# adc_24_bit_arduino-shield_v5.net
KiCad netlist of a schematic drawn in EAGLE
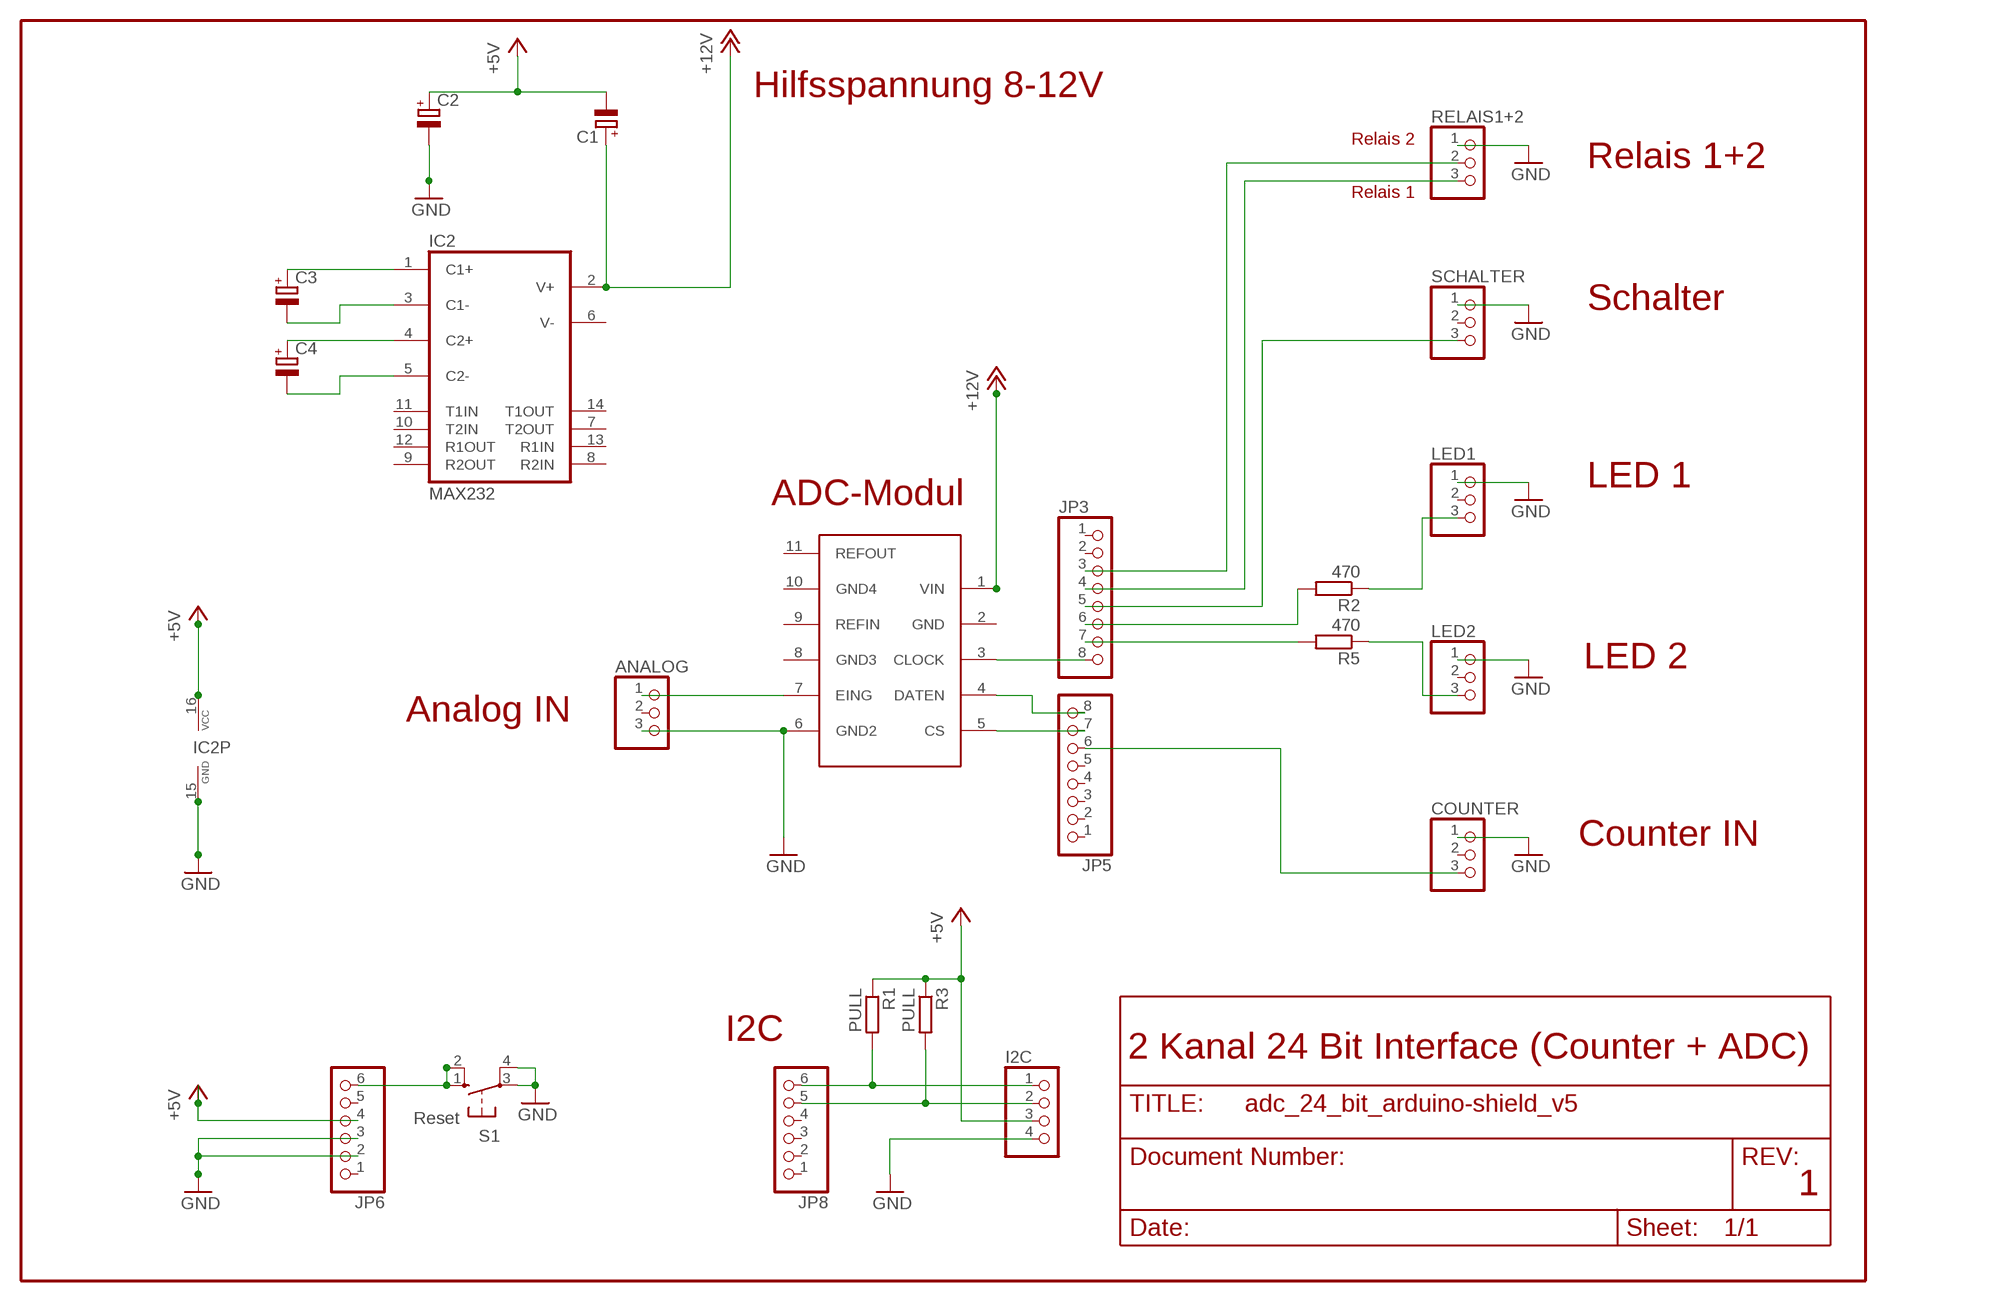
[diagram p0: schematic, sheet 1]

(export (version "E")
  (design (tool "Eeschema 10.0.6"))
  (components
    (comp (ref "ANALOG")
      (value "PINHD-1X3")
      (footprint "eagle-import:1X03")
      (libsource (lib "eagle-import") (part "PINHD-1X3"))
    )
    (comp (ref "C1")
      (value "CPOL-EUE2-4")
      (footprint "eagle-import:E2-4")
      (libsource (lib "eagle-import") (part "CPOL-EUE2-4"))
    )
    (comp (ref "C2")
      (value "CPOL-EUE2-4")
      (footprint "eagle-import:E2-4")
      (libsource (lib "eagle-import") (part "CPOL-EUE2-4"))
    )
    (comp (ref "C3")
      (value "CPOL-EUE2-4")
      (footprint "eagle-import:E2-4")
      (libsource (lib "eagle-import") (part "CPOL-EUE2-4"))
    )
    (comp (ref "C4")
      (value "CPOL-EUE2-4")
      (footprint "eagle-import:E2-4")
      (libsource (lib "eagle-import") (part "CPOL-EUE2-4"))
    )
    (comp (ref "COUNTER")
      (value "PINHD-1X3")
      (footprint "eagle-import:1X03")
      (libsource (lib "eagle-import") (part "PINHD-1X3"))
    )
    (comp (ref "I2C")
      (value "PINHD-1X4")
      (footprint "eagle-import:1X04")
      (libsource (lib "eagle-import") (part "PINHD-1X4"))
    )
    (comp (ref "IC1")
      (value "MODUL")
      (footprint "eagle-import:TEST")
      (libsource (lib "eagle-import") (part "MODUL"))
    )
    (comp (ref "IC2")
      (value "MAX232")
      (footprint "eagle-import:DIL16")
      (libsource (lib "eagle-import") (part "MAX232"))
    )
    (comp (ref "JP3")
      (value "PINHD-1X8CLEANBIG")
      (footprint "eagle-import:1X08-CLEANBIG")
      (libsource (lib "eagle-import") (part "PINHD-1X8CLEANBIG"))
    )
    (comp (ref "JP5")
      (value "PINHD-1X8CLEANBIG")
      (footprint "eagle-import:1X08-CLEANBIG")
      (libsource (lib "eagle-import") (part "PINHD-1X8CLEANBIG"))
    )
    (comp (ref "JP6")
      (value "PINHD-1X6CB")
      (footprint "eagle-import:1X06-CLEANBIG")
      (libsource (lib "eagle-import") (part "PINHD-1X6CB"))
    )
    (comp (ref "JP8")
      (value "PINHD-1X6CB")
      (footprint "eagle-import:1X06-CLEANBIG")
      (libsource (lib "eagle-import") (part "PINHD-1X6CB"))
    )
    (comp (ref "LED1")
      (value "PINHD-1X3")
      (footprint "eagle-import:1X03")
      (libsource (lib "eagle-import") (part "PINHD-1X3"))
    )
    (comp (ref "LED2")
      (value "PINHD-1X3")
      (footprint "eagle-import:1X03")
      (libsource (lib "eagle-import") (part "PINHD-1X3"))
    )
    (comp (ref "R1")
      (value "PULL")
      (footprint "eagle-import:0207_15")
      (libsource (lib "eagle-import") (part "R-EU_0207/15"))
    )
    (comp (ref "R2")
      (value "470")
      (footprint "eagle-import:0207_15")
      (libsource (lib "eagle-import") (part "R-EU_0207/15"))
    )
    (comp (ref "R3")
      (value "PULL")
      (footprint "eagle-import:0207_15")
      (libsource (lib "eagle-import") (part "R-EU_0207/15"))
    )
    (comp (ref "R5")
      (value "470")
      (footprint "eagle-import:0207_15")
      (libsource (lib "eagle-import") (part "R-EU_0207/15"))
    )
    (comp (ref "RELAIS1+2")
      (value "PINHD-1X3")
      (footprint "eagle-import:1X03")
      (libsource (lib "eagle-import") (part "PINHD-1X3"))
    )
    (comp (ref "S1")
      (value "Reset")
      (footprint "eagle-import:B3F-10XX")
      (libsource (lib "eagle-import") (part "10-XX"))
    )
    (comp (ref "SCHALTER")
      (value "PINHD-1X3")
      (footprint "eagle-import:1X03")
      (libsource (lib "eagle-import") (part "PINHD-1X3"))
    )
  )
  (nets
    (net (code "1") (name "+5V") (class "Default")
      (node (ref "C1") (pin "-") (pinfunction "-_-") (pintype "passive"))
      (node (ref "C2") (pin "+") (pinfunction "+_+") (pintype "passive"))
      (node (ref "I2C") (pin "3") (pinfunction "3_3") (pintype "passive"))
      (node (ref "IC2") (pin "16") (pinfunction "VCC_16") (pintype "power_in"))
      (node (ref "JP6") (pin "4") (pinfunction "4_4") (pintype "passive"))
      (node (ref "R1") (pin "1") (pinfunction "1_1") (pintype "passive"))
      (node (ref "R3") (pin "1") (pinfunction "1_1") (pintype "passive"))
    )
    (net (code "2") (name "+12V") (class "Default")
      (node (ref "C1") (pin "+") (pinfunction "+_+") (pintype "passive"))
      (node (ref "IC1") (pin "1") (pinfunction "VIN_1") (pintype "bidirectional"))
      (node (ref "IC2") (pin "2") (pinfunction "V+_2") (pintype "bidirectional"))
    )
    (net (code "3") (name "GND") (class "Default")
      (node (ref "ANALOG") (pin "3") (pinfunction "3_3") (pintype "passive"))
      (node (ref "C2") (pin "-") (pinfunction "-_-") (pintype "passive"))
      (node (ref "COUNTER") (pin "1") (pinfunction "1_1") (pintype "passive"))
      (node (ref "I2C") (pin "4") (pinfunction "4_4") (pintype "passive"))
      (node (ref "IC1") (pin "6") (pinfunction "GND2_6") (pintype "bidirectional"))
      (node (ref "IC2") (pin "15") (pinfunction "GND_15") (pintype "power_in"))
      (node (ref "JP6") (pin "2") (pinfunction "2_2") (pintype "passive"))
      (node (ref "JP6") (pin "3") (pinfunction "3_3") (pintype "passive"))
      (node (ref "LED1") (pin "1") (pinfunction "1_1") (pintype "passive"))
      (node (ref "LED2") (pin "1") (pinfunction "1_1") (pintype "passive"))
      (node (ref "RELAIS1+2") (pin "1") (pinfunction "1_1") (pintype "passive"))
      (node (ref "S1") (pin "3") (pinfunction "P_3") (pintype "passive"))
      (node (ref "S1") (pin "4") (pinfunction "P1_4") (pintype "passive"))
      (node (ref "SCHALTER") (pin "1") (pinfunction "1_1") (pintype "passive"))
    )
    (net (code "4") (name "Net-(COUNTER-Pad3)") (class "Default")
      (node (ref "COUNTER") (pin "3") (pinfunction "3_3") (pintype "passive"))
      (node (ref "JP5") (pin "6") (pinfunction "6_6") (pintype "passive"))
    )
    (net (code "5") (name "Net-(I2C-Pad1)") (class "Default")
      (node (ref "I2C") (pin "1") (pinfunction "1_1") (pintype "passive"))
      (node (ref "JP8") (pin "6") (pinfunction "6_6") (pintype "passive"))
      (node (ref "R1") (pin "2") (pinfunction "2_2") (pintype "passive"))
    )
    (net (code "6") (name "Net-(I2C-Pad2)") (class "Default")
      (node (ref "I2C") (pin "2") (pinfunction "2_2") (pintype "passive"))
      (node (ref "JP8") (pin "5") (pinfunction "5_5") (pintype "passive"))
      (node (ref "R3") (pin "2") (pinfunction "2_2") (pintype "passive"))
    )
    (net (code "7") (name "Net-(IC1-CLOCK)") (class "Default")
      (node (ref "IC1") (pin "3") (pinfunction "CLOCK_3") (pintype "bidirectional"))
      (node (ref "JP3") (pin "8") (pinfunction "8_8") (pintype "passive"))
    )
    (net (code "8") (name "Net-(IC1-CS)") (class "Default")
      (node (ref "IC1") (pin "5") (pinfunction "CS_5") (pintype "bidirectional"))
      (node (ref "JP5") (pin "7") (pinfunction "7_7") (pintype "passive"))
    )
    (net (code "9") (name "Net-(IC1-DATEN)") (class "Default")
      (node (ref "IC1") (pin "4") (pinfunction "DATEN_4") (pintype "bidirectional"))
      (node (ref "JP5") (pin "8") (pinfunction "8_8") (pintype "passive"))
    )
    (net (code "10") (name "Net-(IC1-EING)") (class "Default")
      (node (ref "ANALOG") (pin "1") (pinfunction "1_1") (pintype "passive"))
      (node (ref "IC1") (pin "7") (pinfunction "EING_7") (pintype "bidirectional"))
    )
    (net (code "11") (name "Net-(IC2A-C1+)") (class "Default")
      (node (ref "C3") (pin "+") (pinfunction "+_+") (pintype "passive"))
      (node (ref "IC2") (pin "1") (pinfunction "C1+_1") (pintype "bidirectional"))
    )
    (net (code "12") (name "Net-(IC2A-C1-)") (class "Default")
      (node (ref "C3") (pin "-") (pinfunction "-_-") (pintype "passive"))
      (node (ref "IC2") (pin "3") (pinfunction "C1-_3") (pintype "bidirectional"))
    )
    (net (code "13") (name "Net-(IC2A-C2+)") (class "Default")
      (node (ref "C4") (pin "+") (pinfunction "+_+") (pintype "passive"))
      (node (ref "IC2") (pin "4") (pinfunction "C2+_4") (pintype "bidirectional"))
    )
    (net (code "14") (name "Net-(IC2A-C2-)") (class "Default")
      (node (ref "C4") (pin "-") (pinfunction "-_-") (pintype "passive"))
      (node (ref "IC2") (pin "5") (pinfunction "C2-_5") (pintype "bidirectional"))
    )
    (net (code "15") (name "Net-(JP3-Pad3)") (class "Default")
      (node (ref "JP3") (pin "3") (pinfunction "3_3") (pintype "passive"))
      (node (ref "RELAIS1+2") (pin "2") (pinfunction "2_2") (pintype "passive"))
    )
    (net (code "16") (name "Net-(JP3-Pad4)") (class "Default")
      (node (ref "JP3") (pin "4") (pinfunction "4_4") (pintype "passive"))
      (node (ref "RELAIS1+2") (pin "3") (pinfunction "3_3") (pintype "passive"))
    )
    (net (code "17") (name "Net-(JP3-Pad5)") (class "Default")
      (node (ref "JP3") (pin "5") (pinfunction "5_5") (pintype "passive"))
      (node (ref "SCHALTER") (pin "3") (pinfunction "3_3") (pintype "passive"))
    )
    (net (code "18") (name "Net-(JP3-Pad6)") (class "Default")
      (node (ref "JP3") (pin "6") (pinfunction "6_6") (pintype "passive"))
      (node (ref "R2") (pin "2") (pinfunction "2_2") (pintype "passive"))
    )
    (net (code "19") (name "Net-(JP3-Pad7)") (class "Default")
      (node (ref "JP3") (pin "7") (pinfunction "7_7") (pintype "passive"))
      (node (ref "R5") (pin "2") (pinfunction "2_2") (pintype "passive"))
    )
    (net (code "20") (name "Net-(LED1-Pad3)") (class "Default")
      (node (ref "LED1") (pin "3") (pinfunction "3_3") (pintype "passive"))
      (node (ref "R2") (pin "1") (pinfunction "1_1") (pintype "passive"))
    )
    (net (code "21") (name "Net-(LED2-Pad3)") (class "Default")
      (node (ref "LED2") (pin "3") (pinfunction "3_3") (pintype "passive"))
      (node (ref "R5") (pin "1") (pinfunction "1_1") (pintype "passive"))
    )
    (net (code "22") (name "Net-(S1-S)") (class "Default")
      (node (ref "JP6") (pin "6") (pinfunction "6_6") (pintype "passive"))
      (node (ref "S1") (pin "1") (pinfunction "S_1") (pintype "passive"))
      (node (ref "S1") (pin "2") (pinfunction "S1_2") (pintype "passive"))
    )
    (net (code "23") (name "unconnected-(ANALOG-Pad2)") (class "Default")
      (node (ref "ANALOG") (pin "2") (pinfunction "2_2") (pintype "passive"))
    )
    (net (code "24") (name "unconnected-(COUNTER-Pad2)") (class "Default")
      (node (ref "COUNTER") (pin "2") (pinfunction "2_2") (pintype "passive"))
    )
    (net (code "25") (name "unconnected-(IC1-GND-Pad2)") (class "Default")
      (node (ref "IC1") (pin "2") (pinfunction "GND_2") (pintype "bidirectional"))
    )
    (net (code "26") (name "unconnected-(IC1-GND3-Pad8)") (class "Default")
      (node (ref "IC1") (pin "8") (pinfunction "GND3_8") (pintype "bidirectional"))
    )
    (net (code "27") (name "unconnected-(IC1-GND4-Pad10)") (class "Default")
      (node (ref "IC1") (pin "10") (pinfunction "GND4_10") (pintype "bidirectional"))
    )
    (net (code "28") (name "unconnected-(IC1-REFIN-Pad9)") (class "Default")
      (node (ref "IC1") (pin "9") (pinfunction "REFIN_9") (pintype "bidirectional"))
    )
    (net (code "29") (name "unconnected-(IC1-REFOUT-Pad11)") (class "Default")
      (node (ref "IC1") (pin "11") (pinfunction "REFOUT_11") (pintype "bidirectional"))
    )
    (net (code "30") (name "unconnected-(IC2A-R1IN-Pad13)") (class "Default")
      (node (ref "IC2") (pin "13") (pinfunction "R1IN_13") (pintype "input"))
    )
    (net (code "31") (name "unconnected-(IC2A-R1OUT-Pad12)") (class "Default")
      (node (ref "IC2") (pin "12") (pinfunction "R1OUT_12") (pintype "output"))
    )
    (net (code "32") (name "unconnected-(IC2A-R2IN-Pad8)") (class "Default")
      (node (ref "IC2") (pin "8") (pinfunction "R2IN_8") (pintype "input"))
    )
    (net (code "33") (name "unconnected-(IC2A-R2OUT-Pad9)") (class "Default")
      (node (ref "IC2") (pin "9") (pinfunction "R2OUT_9") (pintype "output"))
    )
    (net (code "34") (name "unconnected-(IC2A-T1IN-Pad11)") (class "Default")
      (node (ref "IC2") (pin "11") (pinfunction "T1IN_11") (pintype "input"))
    )
    (net (code "35") (name "unconnected-(IC2A-T1OUT-Pad14)") (class "Default")
      (node (ref "IC2") (pin "14") (pinfunction "T1OUT_14") (pintype "output"))
    )
    (net (code "36") (name "unconnected-(IC2A-T2IN-Pad10)") (class "Default")
      (node (ref "IC2") (pin "10") (pinfunction "T2IN_10") (pintype "input"))
    )
    (net (code "37") (name "unconnected-(IC2A-T2OUT-Pad7)") (class "Default")
      (node (ref "IC2") (pin "7") (pinfunction "T2OUT_7") (pintype "output"))
    )
    (net (code "38") (name "unconnected-(IC2A-V--Pad6)") (class "Default")
      (node (ref "IC2") (pin "6") (pinfunction "V-_6") (pintype "bidirectional"))
    )
    (net (code "39") (name "unconnected-(JP3-Pad1)") (class "Default")
      (node (ref "JP3") (pin "1") (pinfunction "1_1") (pintype "passive"))
    )
    (net (code "40") (name "unconnected-(JP3-Pad2)") (class "Default")
      (node (ref "JP3") (pin "2") (pinfunction "2_2") (pintype "passive"))
    )
    (net (code "41") (name "unconnected-(JP5-Pad1)") (class "Default")
      (node (ref "JP5") (pin "1") (pinfunction "1_1") (pintype "passive"))
    )
    (net (code "42") (name "unconnected-(JP5-Pad2)") (class "Default")
      (node (ref "JP5") (pin "2") (pinfunction "2_2") (pintype "passive"))
    )
    (net (code "43") (name "unconnected-(JP5-Pad3)") (class "Default")
      (node (ref "JP5") (pin "3") (pinfunction "3_3") (pintype "passive"))
    )
    (net (code "44") (name "unconnected-(JP5-Pad4)") (class "Default")
      (node (ref "JP5") (pin "4") (pinfunction "4_4") (pintype "passive"))
    )
    (net (code "45") (name "unconnected-(JP5-Pad5)") (class "Default")
      (node (ref "JP5") (pin "5") (pinfunction "5_5") (pintype "passive"))
    )
    (net (code "46") (name "unconnected-(JP6-Pad1)") (class "Default")
      (node (ref "JP6") (pin "1") (pinfunction "1_1") (pintype "passive"))
    )
    (net (code "47") (name "unconnected-(JP6-Pad5)") (class "Default")
      (node (ref "JP6") (pin "5") (pinfunction "5_5") (pintype "passive"))
    )
    (net (code "48") (name "unconnected-(JP8-Pad1)") (class "Default")
      (node (ref "JP8") (pin "1") (pinfunction "1_1") (pintype "passive"))
    )
    (net (code "49") (name "unconnected-(JP8-Pad2)") (class "Default")
      (node (ref "JP8") (pin "2") (pinfunction "2_2") (pintype "passive"))
    )
    (net (code "50") (name "unconnected-(JP8-Pad3)") (class "Default")
      (node (ref "JP8") (pin "3") (pinfunction "3_3") (pintype "passive"))
    )
    (net (code "51") (name "unconnected-(JP8-Pad4)") (class "Default")
      (node (ref "JP8") (pin "4") (pinfunction "4_4") (pintype "passive"))
    )
    (net (code "52") (name "unconnected-(LED1-Pad2)") (class "Default")
      (node (ref "LED1") (pin "2") (pinfunction "2_2") (pintype "passive"))
    )
    (net (code "53") (name "unconnected-(LED2-Pad2)") (class "Default")
      (node (ref "LED2") (pin "2") (pinfunction "2_2") (pintype "passive"))
    )
    (net (code "54") (name "unconnected-(SCHALTER-Pad2)") (class "Default")
      (node (ref "SCHALTER") (pin "2") (pinfunction "2_2") (pintype "passive"))
    )
  )
)
